# haasoscope_triggerout_board.net
KiCad netlist of a schematic drawn in EAGLE
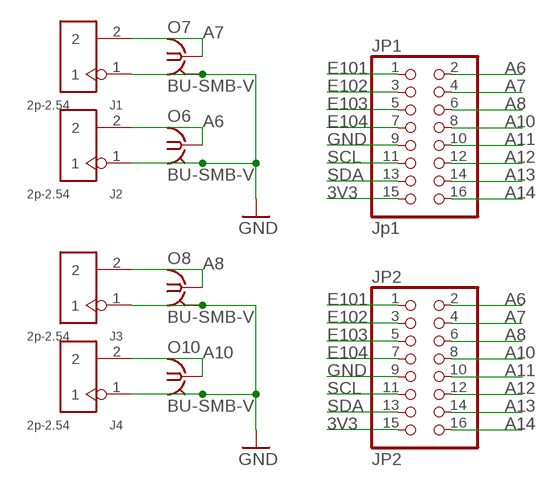
[diagram p0: schematic, sheet 1]

(export (version "E")
  (design (tool "Eeschema 10.0.6"))
  (components
    (comp (ref "J1")
      (value "2p-2.54")
      (footprint "eagle-import:H2-2.54")
      (fields (field (name "MPN") "P125-1102A0BS116A1"))
      (libsource (lib "eagle-import") (part "DIP-BLACK-MALE-HEADER-VERT(2P-2.54)"))
    )
    (comp (ref "J2")
      (value "2p-2.54")
      (footprint "eagle-import:H2-2.54")
      (fields (field (name "MPN") "P125-1102A0BS116A1"))
      (libsource (lib "eagle-import") (part "DIP-BLACK-MALE-HEADER-VERT(2P-2.54)"))
    )
    (comp (ref "J3")
      (value "2p-2.54")
      (footprint "eagle-import:H2-2.54")
      (fields (field (name "MPN") "P125-1102A0BS116A1"))
      (libsource (lib "eagle-import") (part "DIP-BLACK-MALE-HEADER-VERT(2P-2.54)"))
    )
    (comp (ref "J4")
      (value "2p-2.54")
      (footprint "eagle-import:H2-2.54")
      (fields (field (name "MPN") "P125-1102A0BS116A1"))
      (libsource (lib "eagle-import") (part "DIP-BLACK-MALE-HEADER-VERT(2P-2.54)"))
    )
    (comp (ref "JP1")
      (value "Jp1")
      (footprint "eagle-import:2X08")
      (libsource (lib "eagle-import") (part "PINHD-2X8"))
    )
    (comp (ref "JP2")
      (value "JP2")
      (footprint "eagle-import:2X08")
      (libsource (lib "eagle-import") (part "PINHD-2X8"))
    )
    (comp (ref "O6")
      (value "BU-SMB-V")
      (footprint "eagle-import:BU-SMB-V")
      (libsource (lib "eagle-import") (part "BU-SMB-V"))
    )
    (comp (ref "O7")
      (value "BU-SMB-V")
      (footprint "eagle-import:BU-SMB-V")
      (libsource (lib "eagle-import") (part "BU-SMB-V"))
    )
    (comp (ref "O8")
      (value "BU-SMB-V")
      (footprint "eagle-import:BU-SMB-V")
      (libsource (lib "eagle-import") (part "BU-SMB-V"))
    )
    (comp (ref "O10")
      (value "BU-SMB-V")
      (footprint "eagle-import:BU-SMB-V")
      (libsource (lib "eagle-import") (part "BU-SMB-V"))
    )
  )
  (nets
    (net (code "1") (name "/3V3") (class "Default")
      (node (ref "JP1") (pin "15") (pinfunction "15_15") (pintype "passive"))
      (node (ref "JP2") (pin "15") (pinfunction "15_15") (pintype "passive"))
    )
    (net (code "2") (name "/A6") (class "Default")
      (node (ref "J2") (pin "2") (pinfunction "2_2") (pintype "bidirectional"))
      (node (ref "JP1") (pin "2") (pinfunction "2_2") (pintype "passive"))
      (node (ref "JP2") (pin "2") (pinfunction "2_2") (pintype "passive"))
      (node (ref "O6") (pin "1") (pinfunction "1_1") (pintype "passive"))
    )
    (net (code "3") (name "/A7") (class "Default")
      (node (ref "J1") (pin "2") (pinfunction "2_2") (pintype "bidirectional"))
      (node (ref "JP1") (pin "4") (pinfunction "4_4") (pintype "passive"))
      (node (ref "JP2") (pin "4") (pinfunction "4_4") (pintype "passive"))
      (node (ref "O7") (pin "1") (pinfunction "1_1") (pintype "passive"))
    )
    (net (code "4") (name "/A8") (class "Default")
      (node (ref "J3") (pin "2") (pinfunction "2_2") (pintype "bidirectional"))
      (node (ref "JP1") (pin "6") (pinfunction "6_6") (pintype "passive"))
      (node (ref "JP2") (pin "6") (pinfunction "6_6") (pintype "passive"))
      (node (ref "O8") (pin "1") (pinfunction "1_1") (pintype "passive"))
    )
    (net (code "5") (name "/A10") (class "Default")
      (node (ref "J4") (pin "2") (pinfunction "2_2") (pintype "bidirectional"))
      (node (ref "JP1") (pin "8") (pinfunction "8_8") (pintype "passive"))
      (node (ref "JP2") (pin "8") (pinfunction "8_8") (pintype "passive"))
      (node (ref "O10") (pin "1") (pinfunction "1_1") (pintype "passive"))
    )
    (net (code "6") (name "/A11") (class "Default")
      (node (ref "JP1") (pin "10") (pinfunction "10_10") (pintype "passive"))
      (node (ref "JP2") (pin "10") (pinfunction "10_10") (pintype "passive"))
    )
    (net (code "7") (name "/A12") (class "Default")
      (node (ref "JP1") (pin "12") (pinfunction "12_12") (pintype "passive"))
      (node (ref "JP2") (pin "12") (pinfunction "12_12") (pintype "passive"))
    )
    (net (code "8") (name "/A13") (class "Default")
      (node (ref "JP1") (pin "14") (pinfunction "14_14") (pintype "passive"))
      (node (ref "JP2") (pin "14") (pinfunction "14_14") (pintype "passive"))
    )
    (net (code "9") (name "/A14") (class "Default")
      (node (ref "JP1") (pin "16") (pinfunction "16_16") (pintype "passive"))
      (node (ref "JP2") (pin "16") (pinfunction "16_16") (pintype "passive"))
    )
    (net (code "10") (name "/E101") (class "Default")
      (node (ref "JP1") (pin "1") (pinfunction "1_1") (pintype "passive"))
      (node (ref "JP2") (pin "1") (pinfunction "1_1") (pintype "passive"))
    )
    (net (code "11") (name "/E102") (class "Default")
      (node (ref "JP1") (pin "3") (pinfunction "3_3") (pintype "passive"))
      (node (ref "JP2") (pin "3") (pinfunction "3_3") (pintype "passive"))
    )
    (net (code "12") (name "/E103") (class "Default")
      (node (ref "JP1") (pin "5") (pinfunction "5_5") (pintype "passive"))
      (node (ref "JP2") (pin "5") (pinfunction "5_5") (pintype "passive"))
    )
    (net (code "13") (name "/E104") (class "Default")
      (node (ref "JP1") (pin "7") (pinfunction "7_7") (pintype "passive"))
      (node (ref "JP2") (pin "7") (pinfunction "7_7") (pintype "passive"))
    )
    (net (code "14") (name "/SCL") (class "Default")
      (node (ref "JP1") (pin "11") (pinfunction "11_11") (pintype "passive"))
      (node (ref "JP2") (pin "11") (pinfunction "11_11") (pintype "passive"))
    )
    (net (code "15") (name "/SDA") (class "Default")
      (node (ref "JP1") (pin "13") (pinfunction "13_13") (pintype "passive"))
      (node (ref "JP2") (pin "13") (pinfunction "13_13") (pintype "passive"))
    )
    (net (code "16") (name "GND") (class "Default")
      (node (ref "J1") (pin "1") (pinfunction "1_1") (pintype "bidirectional"))
      (node (ref "J2") (pin "1") (pinfunction "1_1") (pintype "bidirectional"))
      (node (ref "J3") (pin "1") (pinfunction "1_1") (pintype "bidirectional"))
      (node (ref "J4") (pin "1") (pinfunction "1_1") (pintype "bidirectional"))
      (node (ref "JP1") (pin "9") (pinfunction "9_9") (pintype "passive"))
      (node (ref "JP2") (pin "9") (pinfunction "9_9") (pintype "passive"))
      (node (ref "O10") (pin "2") (pinfunction "2_2") (pintype "passive"))
      (node (ref "O10") (pin "3") (pinfunction "2_3") (pintype "passive"))
      (node (ref "O10") (pin "4") (pinfunction "2_4") (pintype "passive"))
      (node (ref "O10") (pin "5") (pinfunction "2_5") (pintype "passive"))
      (node (ref "O6") (pin "2") (pinfunction "2_2") (pintype "passive"))
      (node (ref "O6") (pin "3") (pinfunction "2_3") (pintype "passive"))
      (node (ref "O6") (pin "4") (pinfunction "2_4") (pintype "passive"))
      (node (ref "O6") (pin "5") (pinfunction "2_5") (pintype "passive"))
      (node (ref "O7") (pin "2") (pinfunction "2_2") (pintype "passive"))
      (node (ref "O7") (pin "3") (pinfunction "2_3") (pintype "passive"))
      (node (ref "O7") (pin "4") (pinfunction "2_4") (pintype "passive"))
      (node (ref "O7") (pin "5") (pinfunction "2_5") (pintype "passive"))
      (node (ref "O8") (pin "2") (pinfunction "2_2") (pintype "passive"))
      (node (ref "O8") (pin "3") (pinfunction "2_3") (pintype "passive"))
      (node (ref "O8") (pin "4") (pinfunction "2_4") (pintype "passive"))
      (node (ref "O8") (pin "5") (pinfunction "2_5") (pintype "passive"))
    )
  )
)
